# STorM32_NT_BGC_v330m.net
KiCad netlist of a schematic drawn in EAGLE
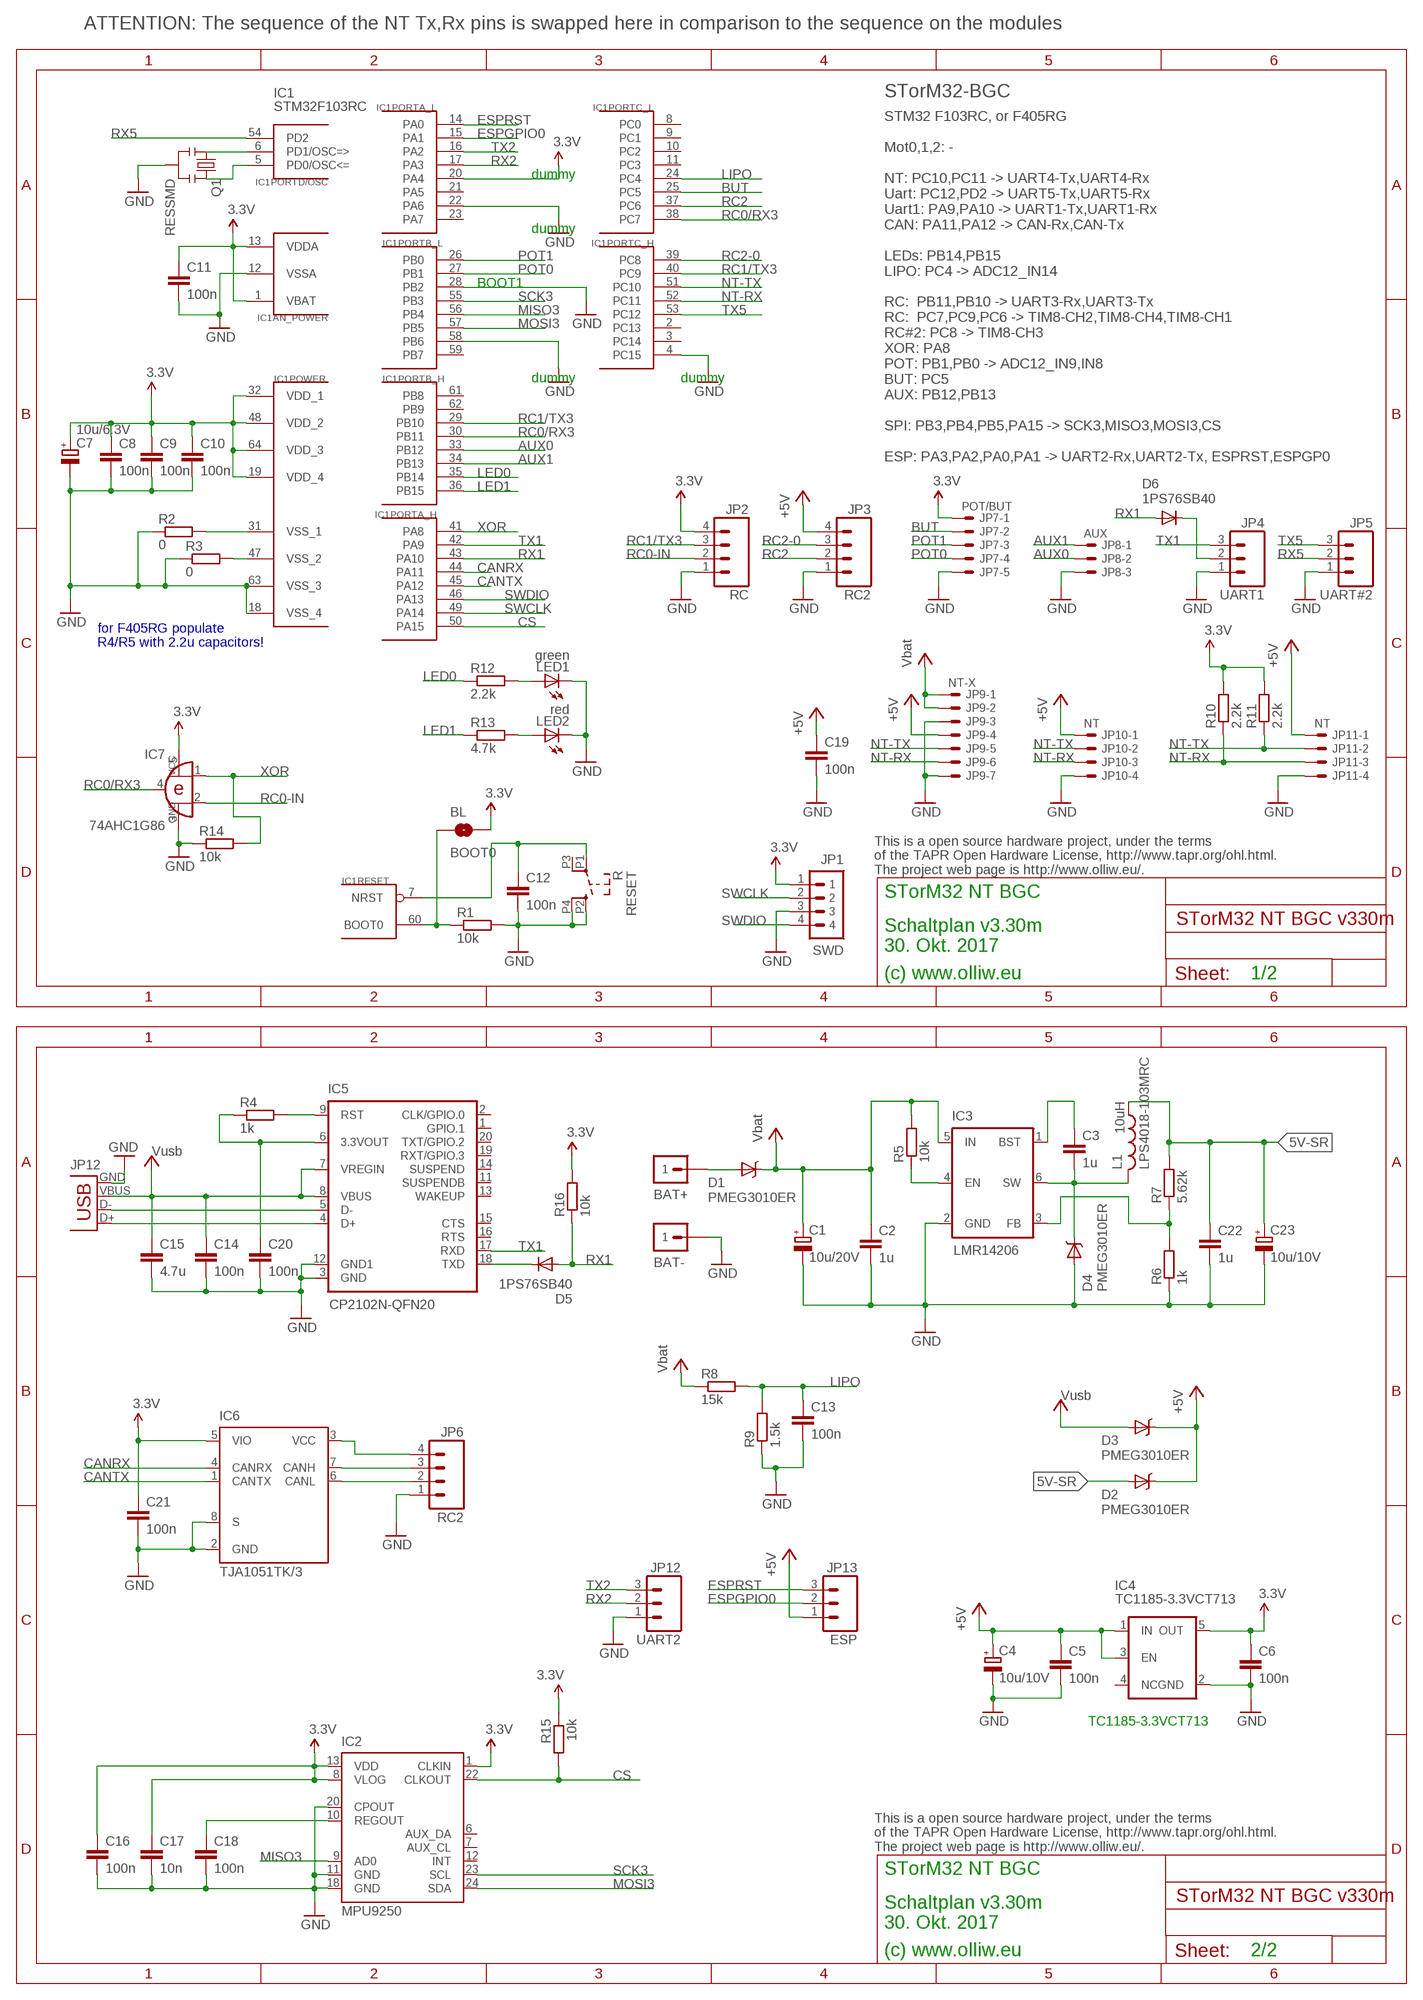
[diagram p0: schematic, sheet 1]

(export (version "E")
  (design (tool "Eeschema 10.0.6"))
  (components
    (comp (ref "BAT+")
      (value "M1X1")
      (footprint "eagle-import:1X1_WITHOUT")
      (libsource (lib "eagle-import") (part "M1X1"))
    )
    (comp (ref "BAT-")
      (value "M1X1")
      (footprint "eagle-import:1X1_WITHOUT")
      (libsource (lib "eagle-import") (part "M1X1"))
    )
    (comp (ref "BL")
      (value "BOOT0")
      (footprint "eagle-import:SJ_2S-NO")
      (libsource (lib "eagle-import") (part "SOLDERJUMPERNO"))
    )
    (comp (ref "C1")
      (value "10u/20V")
      (footprint "eagle-import:SMC_B")
      (libsource (lib "eagle-import") (part "CPOL-EUSMCB"))
    )
    (comp (ref "C2")
      (value "1u")
      (footprint "eagle-import:C0603")
      (libsource (lib "eagle-import") (part "C-EUC0603"))
    )
    (comp (ref "C3")
      (value "1u")
      (footprint "eagle-import:C0603")
      (libsource (lib "eagle-import") (part "C-EUC0603"))
    )
    (comp (ref "C4")
      (value "10u/10V")
      (footprint "eagle-import:SMC_A")
      (libsource (lib "eagle-import") (part "CPOL-EUSMCA"))
    )
    (comp (ref "C5")
      (value "100n")
      (footprint "eagle-import:C0603")
      (libsource (lib "eagle-import") (part "C-EUC0603"))
    )
    (comp (ref "C6")
      (value "100n")
      (footprint "eagle-import:C0402")
      (libsource (lib "eagle-import") (part "C-EUC0402"))
    )
    (comp (ref "C7")
      (value "10u/6.3V")
      (footprint "eagle-import:SMC_A")
      (libsource (lib "eagle-import") (part "CPOL-EUSMCA"))
    )
    (comp (ref "C8")
      (value "100n")
      (footprint "eagle-import:C0402")
      (libsource (lib "eagle-import") (part "C-EUC0402"))
    )
    (comp (ref "C9")
      (value "100n")
      (footprint "eagle-import:C0402")
      (libsource (lib "eagle-import") (part "C-EUC0402"))
    )
    (comp (ref "C10")
      (value "100n")
      (footprint "eagle-import:C0402")
      (libsource (lib "eagle-import") (part "C-EUC0402"))
    )
    (comp (ref "C11")
      (value "100n")
      (footprint "eagle-import:C0402")
      (libsource (lib "eagle-import") (part "C-EUC0402"))
    )
    (comp (ref "C12")
      (value "100n")
      (footprint "eagle-import:C0402")
      (libsource (lib "eagle-import") (part "C-EUC0402"))
    )
    (comp (ref "C13")
      (value "100n")
      (footprint "eagle-import:C0402")
      (libsource (lib "eagle-import") (part "C-EUC0402"))
    )
    (comp (ref "C14")
      (value "100n")
      (footprint "eagle-import:C0402")
      (libsource (lib "eagle-import") (part "C-EUC0402"))
    )
    (comp (ref "C15")
      (value "4.7u")
      (footprint "eagle-import:C0603")
      (libsource (lib "eagle-import") (part "C-EUC0603"))
    )
    (comp (ref "C16")
      (value "100n")
      (footprint "eagle-import:C0402")
      (libsource (lib "eagle-import") (part "C-EUC0402"))
    )
    (comp (ref "C17")
      (value "10n")
      (footprint "eagle-import:C0402")
      (libsource (lib "eagle-import") (part "C-EUC0402"))
    )
    (comp (ref "C18")
      (value "100n")
      (footprint "eagle-import:C0402")
      (libsource (lib "eagle-import") (part "C-EUC0402"))
    )
    (comp (ref "C19")
      (value "100n")
      (footprint "eagle-import:C0402")
      (libsource (lib "eagle-import") (part "C-EUC0402"))
    )
    (comp (ref "C20")
      (value "100n")
      (footprint "eagle-import:C0402")
      (libsource (lib "eagle-import") (part "C-EUC0402"))
    )
    (comp (ref "C21")
      (value "100n")
      (footprint "eagle-import:C0402")
      (libsource (lib "eagle-import") (part "C-EUC0402"))
    )
    (comp (ref "C22")
      (value "1u")
      (footprint "eagle-import:C0603")
      (libsource (lib "eagle-import") (part "C-EUC0603"))
    )
    (comp (ref "C23")
      (value "10u/10V")
      (footprint "eagle-import:SMC_A")
      (libsource (lib "eagle-import") (part "CPOL-EUSMCA"))
    )
    (comp (ref "D1")
      (value "PMEG3010ER")
      (footprint "eagle-import:SOD123W-DIODE")
      (libsource (lib "eagle-import") (part "DIODE-SCHOTTKYSOD123-W"))
    )
    (comp (ref "D2")
      (value "PMEG3010ER")
      (footprint "eagle-import:SOD123W-DIODE")
      (libsource (lib "eagle-import") (part "DIODE-SCHOTTKYSOD123-W"))
    )
    (comp (ref "D3")
      (value "PMEG3010ER")
      (footprint "eagle-import:SOD123W-DIODE")
      (libsource (lib "eagle-import") (part "DIODE-SCHOTTKYSOD123-W"))
    )
    (comp (ref "D4")
      (value "PMEG3010ER")
      (footprint "eagle-import:SOD123W-DIODE")
      (libsource (lib "eagle-import") (part "DIODE-SCHOTTKYSOD123-W"))
    )
    (comp (ref "D5")
      (value "1PS76SB40")
      (footprint "eagle-import:SOD110-R")
      (libsource (lib "eagle-import") (part "DIODE-SOD110-R"))
    )
    (comp (ref "D6")
      (value "1PS76SB40")
      (footprint "eagle-import:SOD110-R")
      (libsource (lib "eagle-import") (part "DIODE-SOD110-R"))
    )
    (comp (ref "IC1")
      (value "STM32F103RCT6")
      (footprint "eagle-import:TQFP64")
      (libsource (lib "eagle-import") (part "STM32F10XRXT6"))
    )
    (comp (ref "IC2")
      (value "MPU9250")
      (footprint "eagle-import:QFN-24-3X3")
      (libsource (lib "eagle-import") (part "IMU3000QFN-24-0.4MIL"))
    )
    (comp (ref "IC3")
      (value "LMR14206")
      (footprint "eagle-import:SOT23-6")
      (libsource (lib "eagle-import") (part "MP2359"))
    )
    (comp (ref "IC4")
      (value "TC1185-3.3VCT713")
      (footprint "eagle-import:SOT23-5")
      (libsource (lib "eagle-import") (part "V_REG_TPS76433SOT23-5"))
    )
    (comp (ref "IC5")
      (value "CP2102N-QFN20")
      (footprint "eagle-import:QFN20-CP2102N")
      (libsource (lib "eagle-import") (part "CP2102N-QFN20"))
    )
    (comp (ref "IC6")
      (value "TJA1051TK/3")
      (footprint "eagle-import:HVSON8")
      (libsource (lib "eagle-import") (part "TJA1051TK/3"))
    )
    (comp (ref "IC7")
      (value "74AHC1G86")
      (footprint "eagle-import:SOT23-5-VER1")
      (libsource (lib "eagle-import") (part "74AHC1G86"))
    )
    (comp (ref "JP1")
      (value "SWD")
      (footprint "eagle-import:4X1_1P27_OCT_BILEX")
      (libsource (lib "eagle-import") (part "P4X1_1P27-OCT_BILEX"))
    )
    (comp (ref "JP2")
      (value "RC")
      (footprint "eagle-import:1X04_NO_SILK")
      (libsource (lib "eagle-import") (part "M041X04_NO_SILK"))
    )
    (comp (ref "JP3")
      (value "RC2")
      (footprint "eagle-import:1X04_NO_SILK")
      (libsource (lib "eagle-import") (part "M041X04_NO_SILK"))
    )
    (comp (ref "JP4")
      (value "UART1")
      (footprint "eagle-import:1X03_NO_SILK")
      (libsource (lib "eagle-import") (part "M031X03_NO_SILK"))
    )
    (comp (ref "JP5")
      (value "UART#2")
      (footprint "eagle-import:1X03_NO_SILK")
      (libsource (lib "eagle-import") (part "M031X03_NO_SILK"))
    )
    (comp (ref "JP6")
      (value "RC2")
      (footprint "eagle-import:1X04_NO_SILK")
      (libsource (lib "eagle-import") (part "M041X04_NO_SILK"))
    )
    (comp (ref "JP7")
      (value "POT/BUT")
      (footprint "eagle-import:SM05B-SRSS-TB")
      (libsource (lib "eagle-import") (part "?M05B-SRSS-TBS"))
    )
    (comp (ref "JP8")
      (value "AUX")
      (footprint "eagle-import:SM03B-SRSS-TB")
      (libsource (lib "eagle-import") (part "?M03B-SRSS-TBS"))
    )
    (comp (ref "JP9")
      (value "NT-X")
      (footprint "eagle-import:SM07B-SRSS-TB")
      (libsource (lib "eagle-import") (part "?M07B-SRSS-TBS"))
    )
    (comp (ref "JP10")
      (value "NT")
      (footprint "eagle-import:SM04B-SRSS-TB")
      (libsource (lib "eagle-import") (part "?M04B-SRSS-TBS"))
    )
    (comp (ref "JP11")
      (value "NT")
      (footprint "eagle-import:SM04B-SRSS-TB")
      (libsource (lib "eagle-import") (part "?M04B-SRSS-TBS"))
    )
    (comp (ref "JP12")
      (value "UART2")
      (footprint "eagle-import:1X03_NO_SILK")
      (libsource (lib "eagle-import") (part "M031X03_NO_SILK"))
    )
    (comp (ref "JP13")
      (value "ESP")
      (footprint "eagle-import:1X03_NO_SILK")
      (libsource (lib "eagle-import") (part "M031X03_NO_SILK"))
    )
    (comp (ref "L1")
      (value "LPS4018-103MRC")
      (footprint "eagle-import:L4X4")
      (libsource (lib "eagle-import") (part "L"))
    )
    (comp (ref "LED1")
      (value "green")
      (footprint "eagle-import:CHIPLED_0603")
      (libsource (lib "eagle-import") (part "LEDCHIPLED_0603"))
    )
    (comp (ref "LED2")
      (value "red")
      (footprint "eagle-import:CHIPLED_0603")
      (libsource (lib "eagle-import") (part "LEDCHIPLED_0603"))
    )
    (comp (ref "Q1")
      (value "RESSMD")
      (footprint "eagle-import:RESONATOR-SMD")
      (libsource (lib "eagle-import") (part "RESONATORSMD"))
    )
    (comp (ref "R1")
      (value "10k")
      (footprint "eagle-import:R0402")
      (libsource (lib "eagle-import") (part "R-EU_R0402"))
    )
    (comp (ref "R2")
      (value "0")
      (footprint "eagle-import:R0402")
      (libsource (lib "eagle-import") (part "R-EU_R0402"))
    )
    (comp (ref "R3")
      (value "0")
      (footprint "eagle-import:R0402")
      (libsource (lib "eagle-import") (part "R-EU_R0402"))
    )
    (comp (ref "R4")
      (value "1k")
      (footprint "eagle-import:R0402")
      (libsource (lib "eagle-import") (part "R-EU_R0402"))
    )
    (comp (ref "R5")
      (value "10k")
      (footprint "eagle-import:R0402")
      (libsource (lib "eagle-import") (part "R-EU_R0402"))
    )
    (comp (ref "R6")
      (value "1k")
      (footprint "eagle-import:R0402")
      (libsource (lib "eagle-import") (part "R-EU_R0402"))
    )
    (comp (ref "R7")
      (value "5.62k")
      (footprint "eagle-import:R0402")
      (libsource (lib "eagle-import") (part "R-EU_R0402"))
    )
    (comp (ref "R8")
      (value "15k")
      (footprint "eagle-import:R0402")
      (libsource (lib "eagle-import") (part "R-EU_R0402"))
    )
    (comp (ref "R9")
      (value "1.5k")
      (footprint "eagle-import:R0402")
      (libsource (lib "eagle-import") (part "R-EU_R0402"))
    )
    (comp (ref "R10")
      (value "2.2k")
      (footprint "eagle-import:R0402")
      (libsource (lib "eagle-import") (part "R-EU_R0402"))
    )
    (comp (ref "R11")
      (value "2.2k")
      (footprint "eagle-import:R0402")
      (libsource (lib "eagle-import") (part "R-EU_R0402"))
    )
    (comp (ref "R12")
      (value "2.2k")
      (footprint "eagle-import:R0402")
      (libsource (lib "eagle-import") (part "R-EU_R0402"))
    )
    (comp (ref "R13")
      (value "4.7k")
      (footprint "eagle-import:R0402")
      (libsource (lib "eagle-import") (part "R-EU_R0402"))
    )
    (comp (ref "R14")
      (value "10k")
      (footprint "eagle-import:R0402")
      (libsource (lib "eagle-import") (part "R-EU_R0402"))
    )
    (comp (ref "R15")
      (value "10k")
      (footprint "eagle-import:R0402")
      (libsource (lib "eagle-import") (part "R-EU_R0402"))
    )
    (comp (ref "R16")
      (value "10k")
      (footprint "eagle-import:R0402")
      (libsource (lib "eagle-import") (part "R-EU_R0402"))
    )
    (comp (ref "RESET")
      (value "R")
      (footprint "eagle-import:TACTILE-SWITCH-SMD-RIGHT-TL1014")
      (libsource (lib "eagle-import") (part "SWITCH-SMD-RIGHT-TL1014"))
    )
    (comp (ref "USB")
      (value "Amphenol 10118192-0001LF")
      (footprint "eagle-import:USB-MICROB")
      (libsource (lib "eagle-import") (part "USB-MICROB"))
    )
  )
  (nets
    (net (code "1") (name "+5V") (class "Default")
      (node (ref "C19") (pin "1") (pinfunction "1_1") (pintype "passive"))
      (node (ref "C4") (pin "+") (pinfunction "+_+") (pintype "passive"))
      (node (ref "C5") (pin "1") (pinfunction "1_1") (pintype "passive"))
      (node (ref "D2") (pin "C") (pinfunction "C_C") (pintype "passive"))
      (node (ref "D3") (pin "C") (pinfunction "C_C") (pintype "passive"))
      (node (ref "IC4") (pin "1") (pinfunction "IN_1") (pintype "power_in"))
      (node (ref "IC4") (pin "3") (pinfunction "EN_3") (pintype "input"))
      (node (ref "JP10") (pin "1") (pinfunction "S_1") (pintype "passive"))
      (node (ref "JP11") (pin "1") (pinfunction "S_1") (pintype "passive"))
      (node (ref "JP13") (pin "1") (pinfunction "1_1") (pintype "passive"))
      (node (ref "JP3") (pin "4") (pinfunction "4_4") (pintype "passive"))
      (node (ref "JP9") (pin "4") (pinfunction "S_4") (pintype "passive"))
    )
    (net (code "2") (name "/AUX0") (class "Default")
      (node (ref "IC1") (pin "33") (pinfunction "PB12_33") (pintype "bidirectional"))
      (node (ref "JP8") (pin "2") (pinfunction "S_2") (pintype "passive"))
    )
    (net (code "3") (name "/AUX1") (class "Default")
      (node (ref "IC1") (pin "34") (pinfunction "PB13_34") (pintype "bidirectional"))
      (node (ref "JP8") (pin "1") (pinfunction "S_1") (pintype "passive"))
    )
    (net (code "4") (name "/BUT") (class "Default")
      (node (ref "IC1") (pin "25") (pinfunction "PC5_25") (pintype "bidirectional"))
      (node (ref "JP7") (pin "2") (pinfunction "S_2") (pintype "passive"))
    )
    (net (code "5") (name "/CANRX") (class "Default")
      (node (ref "IC1") (pin "44") (pinfunction "PA11_44") (pintype "bidirectional"))
      (node (ref "IC6") (pin "4") (pinfunction "CANRX_4") (pintype "output"))
    )
    (net (code "6") (name "/CANTX") (class "Default")
      (node (ref "IC1") (pin "45") (pinfunction "PA12_45") (pintype "bidirectional"))
      (node (ref "IC6") (pin "1") (pinfunction "CANTX_1") (pintype "input"))
    )
    (net (code "7") (name "/CS") (class "Default")
      (node (ref "IC1") (pin "50") (pinfunction "PA15_50") (pintype "bidirectional"))
      (node (ref "IC2") (pin "22") (pinfunction "CLKOUT_22") (pintype "bidirectional"))
      (node (ref "R15") (pin "2") (pinfunction "2_2") (pintype "passive"))
    )
    (net (code "8") (name "/ESPGPIO0") (class "Default")
      (node (ref "IC1") (pin "15") (pinfunction "PA1_15") (pintype "bidirectional"))
      (node (ref "JP13") (pin "2") (pinfunction "2_2") (pintype "passive"))
    )
    (net (code "9") (name "/ESPRST") (class "Default")
      (node (ref "IC1") (pin "14") (pinfunction "PA0_14") (pintype "bidirectional"))
      (node (ref "JP13") (pin "3") (pinfunction "3_3") (pintype "passive"))
    )
    (net (code "10") (name "/LED0") (class "Default")
      (node (ref "IC1") (pin "35") (pinfunction "PB14_35") (pintype "bidirectional"))
      (node (ref "R12") (pin "1") (pinfunction "1_1") (pintype "passive"))
    )
    (net (code "11") (name "/LED1") (class "Default")
      (node (ref "IC1") (pin "36") (pinfunction "PB15_36") (pintype "bidirectional"))
      (node (ref "R13") (pin "1") (pinfunction "1_1") (pintype "passive"))
    )
    (net (code "12") (name "/LIPO") (class "Default")
      (node (ref "C13") (pin "1") (pinfunction "1_1") (pintype "passive"))
      (node (ref "IC1") (pin "24") (pinfunction "PC4_24") (pintype "bidirectional"))
      (node (ref "R8") (pin "2") (pinfunction "2_2") (pintype "passive"))
      (node (ref "R9") (pin "2") (pinfunction "2_2") (pintype "passive"))
    )
    (net (code "13") (name "/MISO3") (class "Default")
      (node (ref "IC1") (pin "56") (pinfunction "PB4_56") (pintype "bidirectional"))
      (node (ref "IC2") (pin "9") (pinfunction "AD0_9") (pintype "bidirectional"))
    )
    (net (code "14") (name "/MOSI3") (class "Default")
      (node (ref "IC1") (pin "57") (pinfunction "PB5_57") (pintype "bidirectional"))
      (node (ref "IC2") (pin "24") (pinfunction "SDA_24") (pintype "bidirectional"))
    )
    (net (code "15") (name "/NT-RX") (class "Default")
      (node (ref "IC1") (pin "52") (pinfunction "PC11_52") (pintype "bidirectional"))
      (node (ref "JP10") (pin "3") (pinfunction "S_3") (pintype "passive"))
      (node (ref "JP11") (pin "3") (pinfunction "S_3") (pintype "passive"))
      (node (ref "JP9") (pin "6") (pinfunction "S_6") (pintype "passive"))
      (node (ref "R10") (pin "1") (pinfunction "1_1") (pintype "passive"))
    )
    (net (code "16") (name "/NT-TX") (class "Default")
      (node (ref "IC1") (pin "51") (pinfunction "PC10_51") (pintype "bidirectional"))
      (node (ref "JP10") (pin "2") (pinfunction "S_2") (pintype "passive"))
      (node (ref "JP11") (pin "2") (pinfunction "S_2") (pintype "passive"))
      (node (ref "JP9") (pin "5") (pinfunction "S_5") (pintype "passive"))
      (node (ref "R11") (pin "1") (pinfunction "1_1") (pintype "passive"))
    )
    (net (code "17") (name "/POT0") (class "Default")
      (node (ref "IC1") (pin "27") (pinfunction "PB1_27") (pintype "bidirectional"))
      (node (ref "JP7") (pin "4") (pinfunction "S_4") (pintype "passive"))
    )
    (net (code "18") (name "/POT1") (class "Default")
      (node (ref "IC1") (pin "26") (pinfunction "PB0_26") (pintype "bidirectional"))
      (node (ref "JP7") (pin "3") (pinfunction "S_3") (pintype "passive"))
    )
    (net (code "19") (name "/RC0-IN") (class "Default")
      (node (ref "IC7") (pin "2") (pinfunction "I1_2") (pintype "input"))
      (node (ref "JP2") (pin "2") (pinfunction "2_2") (pintype "passive"))
    )
    (net (code "20") (name "/RC0{slash}RX3") (class "Default")
      (node (ref "IC1") (pin "30") (pinfunction "PB11_30") (pintype "bidirectional"))
      (node (ref "IC1") (pin "38") (pinfunction "PC7_38") (pintype "bidirectional"))
      (node (ref "IC7") (pin "4") (pinfunction "O_4") (pintype "output"))
    )
    (net (code "21") (name "/RC1{slash}TX3") (class "Default")
      (node (ref "IC1") (pin "29") (pinfunction "PB10_29") (pintype "bidirectional"))
      (node (ref "IC1") (pin "40") (pinfunction "PC9_40") (pintype "bidirectional"))
      (node (ref "JP2") (pin "3") (pinfunction "3_3") (pintype "passive"))
    )
    (net (code "22") (name "/RC2") (class "Default")
      (node (ref "IC1") (pin "37") (pinfunction "PC6_37") (pintype "bidirectional"))
      (node (ref "JP3") (pin "2") (pinfunction "2_2") (pintype "passive"))
    )
    (net (code "23") (name "/RC2-0") (class "Default")
      (node (ref "IC1") (pin "39") (pinfunction "PC8_39") (pintype "bidirectional"))
      (node (ref "JP3") (pin "3") (pinfunction "3_3") (pintype "passive"))
    )
    (net (code "24") (name "/RX1") (class "Default")
      (node (ref "D5") (pin "A") (pinfunction "A_A") (pintype "passive"))
      (node (ref "D6") (pin "A") (pinfunction "A_A") (pintype "passive"))
      (node (ref "IC1") (pin "43") (pinfunction "PA10_43") (pintype "bidirectional"))
      (node (ref "R16") (pin "1") (pinfunction "1_1") (pintype "passive"))
    )
    (net (code "25") (name "/RX2") (class "Default")
      (node (ref "IC1") (pin "17") (pinfunction "PA3_17") (pintype "bidirectional"))
      (node (ref "JP12") (pin "2") (pinfunction "2_2") (pintype "passive"))
    )
    (net (code "26") (name "/RX5") (class "Default")
      (node (ref "IC1") (pin "54") (pinfunction "PD2_54") (pintype "bidirectional"))
      (node (ref "JP5") (pin "2") (pinfunction "2_2") (pintype "passive"))
    )
    (net (code "27") (name "/SCK3") (class "Default")
      (node (ref "IC1") (pin "55") (pinfunction "PB3_55") (pintype "bidirectional"))
      (node (ref "IC2") (pin "23") (pinfunction "SCL_23") (pintype "bidirectional"))
    )
    (net (code "28") (name "/SWCLK") (class "Default")
      (node (ref "IC1") (pin "49") (pinfunction "PA14_49") (pintype "bidirectional"))
      (node (ref "JP1") (pin "2") (pinfunction "2_2") (pintype "passive"))
    )
    (net (code "29") (name "/SWDIO") (class "Default")
      (node (ref "IC1") (pin "46") (pinfunction "PA13_46") (pintype "bidirectional"))
      (node (ref "JP1") (pin "4") (pinfunction "4_4") (pintype "passive"))
    )
    (net (code "30") (name "/TX1") (class "Default")
      (node (ref "IC1") (pin "42") (pinfunction "PA9_42") (pintype "bidirectional"))
      (node (ref "IC5") (pin "17") (pinfunction "RXD_17") (pintype "input"))
      (node (ref "JP4") (pin "3") (pinfunction "3_3") (pintype "passive"))
    )
    (net (code "31") (name "/TX2") (class "Default")
      (node (ref "IC1") (pin "16") (pinfunction "PA2_16") (pintype "bidirectional"))
      (node (ref "JP12") (pin "3") (pinfunction "3_3") (pintype "passive"))
    )
    (net (code "32") (name "/TX5") (class "Default")
      (node (ref "IC1") (pin "53") (pinfunction "PC12_53") (pintype "bidirectional"))
      (node (ref "JP5") (pin "3") (pinfunction "3_3") (pintype "passive"))
    )
    (net (code "33") (name "/XOR") (class "Default")
      (node (ref "IC1") (pin "41") (pinfunction "PA8_41") (pintype "bidirectional"))
      (node (ref "IC7") (pin "1") (pinfunction "I0_1") (pintype "input"))
      (node (ref "R14") (pin "2") (pinfunction "2_2") (pintype "passive"))
    )
    (net (code "34") (name "3.3V") (class "Default")
      (node (ref "BL") (pin "2") (pinfunction "2_2") (pintype "passive"))
      (node (ref "C10") (pin "1") (pinfunction "1_1") (pintype "passive"))
      (node (ref "C11") (pin "1") (pinfunction "1_1") (pintype "passive"))
      (node (ref "C16") (pin "1") (pinfunction "1_1") (pintype "passive"))
      (node (ref "C17") (pin "1") (pinfunction "1_1") (pintype "passive"))
      (node (ref "C21") (pin "1") (pinfunction "1_1") (pintype "passive"))
      (node (ref "C6") (pin "1") (pinfunction "1_1") (pintype "passive"))
      (node (ref "C7") (pin "+") (pinfunction "+_+") (pintype "passive"))
      (node (ref "C8") (pin "1") (pinfunction "1_1") (pintype "passive"))
      (node (ref "C9") (pin "1") (pinfunction "1_1") (pintype "passive"))
      (node (ref "IC1") (pin "1") (pinfunction "VBAT_1") (pintype "power_in"))
      (node (ref "IC1") (pin "13") (pinfunction "VDDA_13") (pintype "power_in"))
      (node (ref "IC1") (pin "19") (pinfunction "VDD_4_19") (pintype "power_in"))
      (node (ref "IC1") (pin "20") (pinfunction "PA4_20") (pintype "bidirectional"))
      (node (ref "IC1") (pin "32") (pinfunction "VDD_1_32") (pintype "power_in"))
      (node (ref "IC1") (pin "48") (pinfunction "VDD_2_48") (pintype "power_in"))
      (node (ref "IC1") (pin "64") (pinfunction "VDD_3_64") (pintype "power_in"))
      (node (ref "IC2") (pin "1") (pinfunction "CLKIN_1") (pintype "bidirectional"))
      (node (ref "IC2") (pin "13") (pinfunction "VDD_13") (pintype "bidirectional"))
      (node (ref "IC2") (pin "8") (pinfunction "VLOG_8") (pintype "bidirectional"))
      (node (ref "IC4") (pin "5") (pinfunction "OUT_5") (pintype "output"))
      (node (ref "IC6") (pin "5") (pinfunction "VIO_5") (pintype "power_in"))
      (node (ref "IC7") (pin "5") (pinfunction "VCC_5") (pintype "power_in"))
      (node (ref "JP1") (pin "1") (pinfunction "1_1") (pintype "passive"))
      (node (ref "JP2") (pin "4") (pinfunction "4_4") (pintype "passive"))
      (node (ref "JP7") (pin "1") (pinfunction "S_1") (pintype "passive"))
      (node (ref "R10") (pin "2") (pinfunction "2_2") (pintype "passive"))
      (node (ref "R11") (pin "2") (pinfunction "2_2") (pintype "passive"))
      (node (ref "R15") (pin "1") (pinfunction "1_1") (pintype "passive"))
      (node (ref "R16") (pin "2") (pinfunction "2_2") (pintype "passive"))
    )
    (net (code "35") (name "5V-SR") (class "Default")
      (node (ref "C22") (pin "1") (pinfunction "1_1") (pintype "passive"))
      (node (ref "C23") (pin "+") (pinfunction "+_+") (pintype "passive"))
      (node (ref "D2") (pin "A") (pinfunction "A_A") (pintype "passive"))
      (node (ref "L1") (pin "1") (pinfunction "1_1") (pintype "passive"))
      (node (ref "R7") (pin "2") (pinfunction "2_2") (pintype "passive"))
    )
    (net (code "36") (name "GND") (class "Default")
      (node (ref "BAT-") (pin "1") (pinfunction "1_1") (pintype "passive"))
      (node (ref "C1") (pin "-") (pinfunction "-_-") (pintype "passive"))
      (node (ref "C10") (pin "2") (pinfunction "2_2") (pintype "passive"))
      (node (ref "C11") (pin "2") (pinfunction "2_2") (pintype "passive"))
      (node (ref "C12") (pin "2") (pinfunction "2_2") (pintype "passive"))
      (node (ref "C13") (pin "2") (pinfunction "2_2") (pintype "passive"))
      (node (ref "C14") (pin "2") (pinfunction "2_2") (pintype "passive"))
      (node (ref "C15") (pin "2") (pinfunction "2_2") (pintype "passive"))
      (node (ref "C16") (pin "2") (pinfunction "2_2") (pintype "passive"))
      (node (ref "C17") (pin "2") (pinfunction "2_2") (pintype "passive"))
      (node (ref "C18") (pin "2") (pinfunction "2_2") (pintype "passive"))
      (node (ref "C19") (pin "2") (pinfunction "2_2") (pintype "passive"))
      (node (ref "C2") (pin "2") (pinfunction "2_2") (pintype "passive"))
      (node (ref "C20") (pin "2") (pinfunction "2_2") (pintype "passive"))
      (node (ref "C21") (pin "2") (pinfunction "2_2") (pintype "passive"))
      (node (ref "C22") (pin "2") (pinfunction "2_2") (pintype "passive"))
      (node (ref "C23") (pin "-") (pinfunction "-_-") (pintype "passive"))
      (node (ref "C4") (pin "-") (pinfunction "-_-") (pintype "passive"))
      (node (ref "C5") (pin "2") (pinfunction "2_2") (pintype "passive"))
      (node (ref "C6") (pin "2") (pinfunction "2_2") (pintype "passive"))
      (node (ref "C7") (pin "-") (pinfunction "-_-") (pintype "passive"))
      (node (ref "C8") (pin "2") (pinfunction "2_2") (pintype "passive"))
      (node (ref "C9") (pin "2") (pinfunction "2_2") (pintype "passive"))
      (node (ref "D4") (pin "A") (pinfunction "A_A") (pintype "passive"))
      (node (ref "IC1") (pin "12") (pinfunction "VSSA_12") (pintype "power_in"))
      (node (ref "IC1") (pin "18") (pinfunction "VSS_4_18") (pintype "power_in"))
      (node (ref "IC1") (pin "22") (pinfunction "PA6_22") (pintype "bidirectional"))
      (node (ref "IC1") (pin "28") (pinfunction "PB2_28") (pintype "bidirectional"))
      (node (ref "IC1") (pin "4") (pinfunction "PC15_4") (pintype "bidirectional"))
      (node (ref "IC1") (pin "58") (pinfunction "PB6_58") (pintype "bidirectional"))
      (node (ref "IC1") (pin "63") (pinfunction "VSS_3_63") (pintype "power_in"))
      (node (ref "IC2") (pin "11") (pinfunction "GND_11") (pintype "bidirectional"))
      (node (ref "IC2") (pin "18") (pinfunction "GND_18") (pintype "bidirectional"))
      (node (ref "IC2") (pin "20") (pinfunction "CPOUT_20") (pintype "bidirectional"))
      (node (ref "IC3") (pin "2") (pinfunction "GND_2") (pintype "power_in"))
      (node (ref "IC4") (pin "2") (pinfunction "GND_2") (pintype "power_in"))
      (node (ref "IC5") (pin "12") (pinfunction "GND1_12") (pintype "power_in"))
      (node (ref "IC5") (pin "3") (pinfunction "GND_3") (pintype "power_in"))
      (node (ref "IC6") (pin "2") (pinfunction "GND_2") (pintype "power_in"))
      (node (ref "IC6") (pin "8") (pinfunction "S_8") (pintype "input"))
      (node (ref "IC7") (pin "3") (pinfunction "GND_3") (pintype "power_in"))
      (node (ref "JP1") (pin "3") (pinfunction "3_3") (pintype "passive"))
      (node (ref "JP10") (pin "4") (pinfunction "S_4") (pintype "passive"))
      (node (ref "JP11") (pin "4") (pinfunction "S_4") (pintype "passive"))
      (node (ref "JP12") (pin "1") (pinfunction "1_1") (pintype "passive"))
      (node (ref "JP2") (pin "1") (pinfunction "1_1") (pintype "passive"))
      (node (ref "JP3") (pin "1") (pinfunction "1_1") (pintype "passive"))
      (node (ref "JP4") (pin "1") (pinfunction "1_1") (pintype "passive"))
      (node (ref "JP5") (pin "1") (pinfunction "1_1") (pintype "passive"))
      (node (ref "JP6") (pin "1") (pinfunction "1_1") (pintype "passive"))
      (node (ref "JP7") (pin "5") (pinfunction "S_5") (pintype "passive"))
      (node (ref "JP8") (pin "3") (pinfunction "S_3") (pintype "passive"))
      (node (ref "JP9") (pin "3") (pinfunction "S_3") (pintype "passive"))
      (node (ref "JP9") (pin "7") (pinfunction "S_7") (pintype "passive"))
      (node (ref "LED1") (pin "C") (pinfunction "C_C") (pintype "passive"))
      (node (ref "LED2") (pin "C") (pinfunction "C_C") (pintype "passive"))
      (node (ref "Q1") (pin "2") (pinfunction "2_2") (pintype "passive"))
      (node (ref "R1") (pin "2") (pinfunction "2_2") (pintype "passive"))
      (node (ref "R14") (pin "1") (pinfunction "1_1") (pintype "passive"))
      (node (ref "R2") (pin "1") (pinfunction "1_1") (pintype "passive"))
      (node (ref "R3") (pin "1") (pinfunction "1_1") (pintype "passive"))
      (node (ref "R6") (pin "1") (pinfunction "1_1") (pintype "passive"))
      (node (ref "R9") (pin "1") (pinfunction "1_1") (pintype "passive"))
      (node (ref "RESET") (pin "P2") (pinfunction "1_P2") (pintype "passive"))
      (node (ref "RESET") (pin "P4") (pinfunction "2_P4") (pintype "passive"))
      (node (ref "USB") (pin "GND") (pinfunction "GND_GND") (pintype "bidirectional"))
    )
    (net (code "37") (name "Net-(BAT+-Pad1)") (class "Default")
      (node (ref "BAT+") (pin "1") (pinfunction "1_1") (pintype "passive"))
      (node (ref "D1") (pin "A") (pinfunction "A_A") (pintype "passive"))
    )
    (net (code "38") (name "Net-(D6-PadC)") (class "Default")
      (node (ref "D6") (pin "C") (pinfunction "C_C") (pintype "passive"))
      (node (ref "JP4") (pin "2") (pinfunction "2_2") (pintype "passive"))
    )
    (net (code "39") (name "Net-(IC1H-PD0{slash}OSC<=)") (class "Default")
      (node (ref "IC1") (pin "5") (pinfunction "PD0/OSC<=_5") (pintype "bidirectional"))
      (node (ref "Q1") (pin "3") (pinfunction "3_3") (pintype "passive"))
    )
    (net (code "40") (name "Net-(IC1H-PD1{slash}OSC=>)") (class "Default")
      (node (ref "IC1") (pin "6") (pinfunction "PD1/OSC=>_6") (pintype "bidirectional"))
      (node (ref "Q1") (pin "1") (pinfunction "1_1") (pintype "passive"))
    )
    (net (code "41") (name "Net-(IC1I-VSS_1)") (class "Default")
      (node (ref "IC1") (pin "31") (pinfunction "VSS_1_31") (pintype "power_in"))
      (node (ref "R2") (pin "2") (pinfunction "2_2") (pintype "passive"))
    )
    (net (code "42") (name "Net-(IC1I-VSS_2)") (class "Default")
      (node (ref "IC1") (pin "47") (pinfunction "VSS_2_47") (pintype "power_in"))
      (node (ref "R3") (pin "2") (pinfunction "2_2") (pintype "passive"))
    )
    (net (code "43") (name "Net-(IC1J-BOOT0)") (class "Default")
      (node (ref "BL") (pin "1") (pinfunction "1_1") (pintype "passive"))
      (node (ref "IC1") (pin "60") (pinfunction "BOOT0_60") (pintype "input"))
      (node (ref "R1") (pin "1") (pinfunction "1_1") (pintype "passive"))
    )
    (net (code "44") (name "Net-(IC1J-NRST)") (class "Default")
      (node (ref "C12") (pin "1") (pinfunction "1_1") (pintype "passive"))
      (node (ref "IC1") (pin "7") (pinfunction "NRST_7") (pintype "input"))
      (node (ref "RESET") (pin "P1") (pinfunction "3_P1") (pintype "passive"))
    )
    (net (code "45") (name "Net-(IC2-REGOUT)") (class "Default")
      (node (ref "C18") (pin "1") (pinfunction "1_1") (pintype "passive"))
      (node (ref "IC2") (pin "10") (pinfunction "REGOUT_10") (pintype "bidirectional"))
    )
    (net (code "46") (name "Net-(IC3-BST)") (class "Default")
      (node (ref "C3") (pin "1") (pinfunction "1_1") (pintype "passive"))
      (node (ref "IC3") (pin "1") (pinfunction "BST_1") (pintype "output"))
    )
    (net (code "47") (name "Net-(IC3-EN)") (class "Default")
      (node (ref "IC3") (pin "4") (pinfunction "EN_4") (pintype "input"))
      (node (ref "R5") (pin "1") (pinfunction "1_1") (pintype "passive"))
    )
    (net (code "48") (name "Net-(IC3-FB)") (class "Default")
      (node (ref "IC3") (pin "3") (pinfunction "FB_3") (pintype "input"))
      (node (ref "R6") (pin "2") (pinfunction "2_2") (pintype "passive"))
      (node (ref "R7") (pin "1") (pinfunction "1_1") (pintype "passive"))
    )
    (net (code "49") (name "Net-(IC3-SW)") (class "Default")
      (node (ref "C3") (pin "2") (pinfunction "2_2") (pintype "passive"))
      (node (ref "D4") (pin "C") (pinfunction "C_C") (pintype "passive"))
      (node (ref "IC3") (pin "6") (pinfunction "SW_6") (pintype "output"))
      (node (ref "L1") (pin "2") (pinfunction "2_2") (pintype "passive"))
    )
    (net (code "50") (name "Net-(IC5-3.3VOUT)") (class "Default")
      (node (ref "C20") (pin "1") (pinfunction "1_1") (pintype "passive"))
      (node (ref "IC5") (pin "6") (pinfunction "3.3VOUT_6") (pintype "power_in"))
      (node (ref "R4") (pin "1") (pinfunction "1_1") (pintype "passive"))
    )
    (net (code "51") (name "Net-(IC5-D+)") (class "Default")
      (node (ref "IC5") (pin "4") (pinfunction "D+_4") (pintype "bidirectional"))
      (node (ref "USB") (pin "D+") (pinfunction "D+_D+") (pintype "bidirectional"))
    )
    (net (code "52") (name "Net-(IC5-D-)") (class "Default")
      (node (ref "IC5") (pin "5") (pinfunction "D-_5") (pintype "bidirectional"))
      (node (ref "USB") (pin "D-") (pinfunction "D-_D-") (pintype "bidirectional"))
    )
    (net (code "53") (name "Net-(IC5-RST)") (class "Default")
      (node (ref "IC5") (pin "9") (pinfunction "RST_9") (pintype "input"))
      (node (ref "R4") (pin "2") (pinfunction "2_2") (pintype "passive"))
    )
    (net (code "54") (name "Net-(IC5-TXD)") (class "Default")
      (node (ref "D5") (pin "C") (pinfunction "C_C") (pintype "passive"))
      (node (ref "IC5") (pin "18") (pinfunction "TXD_18") (pintype "output"))
    )
    (net (code "55") (name "Net-(IC6-CANH)") (class "Default")
      (node (ref "IC6") (pin "7") (pinfunction "CANH_7") (pintype "bidirectional"))
      (node (ref "JP6") (pin "3") (pinfunction "3_3") (pintype "passive"))
    )
    (net (code "56") (name "Net-(IC6-CANL)") (class "Default")
      (node (ref "IC6") (pin "6") (pinfunction "CANL_6") (pintype "bidirectional"))
      (node (ref "JP6") (pin "2") (pinfunction "2_2") (pintype "passive"))
    )
    (net (code "57") (name "Net-(IC6-VCC)") (class "Default")
      (node (ref "IC6") (pin "3") (pinfunction "VCC_3") (pintype "power_in"))
      (node (ref "JP6") (pin "4") (pinfunction "4_4") (pintype "passive"))
    )
    (net (code "58") (name "Net-(LED1-PadA)") (class "Default")
      (node (ref "LED1") (pin "A") (pinfunction "A_A") (pintype "passive"))
      (node (ref "R12") (pin "2") (pinfunction "2_2") (pintype "passive"))
    )
    (net (code "59") (name "Net-(LED2-PadA)") (class "Default")
      (node (ref "LED2") (pin "A") (pinfunction "A_A") (pintype "passive"))
      (node (ref "R13") (pin "2") (pinfunction "2_2") (pintype "passive"))
    )
    (net (code "60") (name "Vbat") (class "Default")
      (node (ref "C1") (pin "+") (pinfunction "+_+") (pintype "passive"))
      (node (ref "C2") (pin "1") (pinfunction "1_1") (pintype "passive"))
      (node (ref "D1") (pin "C") (pinfunction "C_C") (pintype "passive"))
      (node (ref "IC3") (pin "5") (pinfunction "IN_5") (pintype "power_in"))
      (node (ref "JP9") (pin "1") (pinfunction "S_1") (pintype "passive"))
      (node (ref "JP9") (pin "2") (pinfunction "S_2") (pintype "passive"))
      (node (ref "R5") (pin "2") (pinfunction "2_2") (pintype "passive"))
      (node (ref "R8") (pin "1") (pinfunction "1_1") (pintype "passive"))
    )
    (net (code "61") (name "Vusb") (class "Default")
      (node (ref "C14") (pin "1") (pinfunction "1_1") (pintype "passive"))
      (node (ref "C15") (pin "1") (pinfunction "1_1") (pintype "passive"))
      (node (ref "D3") (pin "A") (pinfunction "A_A") (pintype "passive"))
      (node (ref "IC5") (pin "7") (pinfunction "VREGIN_7") (pintype "power_in"))
      (node (ref "IC5") (pin "8") (pinfunction "VBUS_8") (pintype "input"))
      (node (ref "USB") (pin "VBUS") (pinfunction "VBUS_VBUS") (pintype "bidirectional"))
    )
    (net (code "62") (name "unconnected-(IC1C-PA5-Pad21)") (class "Default")
      (node (ref "IC1") (pin "21") (pinfunction "PA5_21") (pintype "bidirectional"))
    )
    (net (code "63") (name "unconnected-(IC1C-PA7-Pad23)") (class "Default")
      (node (ref "IC1") (pin "23") (pinfunction "PA7_23") (pintype "bidirectional"))
    )
    (net (code "64") (name "unconnected-(IC1D-PB8-Pad61)") (class "Default")
      (node (ref "IC1") (pin "61") (pinfunction "PB8_61") (pintype "bidirectional"))
    )
    (net (code "65") (name "unconnected-(IC1D-PB9-Pad62)") (class "Default")
      (node (ref "IC1") (pin "62") (pinfunction "PB9_62") (pintype "bidirectional"))
    )
    (net (code "66") (name "unconnected-(IC1E-PB7-Pad59)") (class "Default")
      (node (ref "IC1") (pin "59") (pinfunction "PB7_59") (pintype "bidirectional"))
    )
    (net (code "67") (name "unconnected-(IC1F-PC13-Pad2)") (class "Default")
      (node (ref "IC1") (pin "2") (pinfunction "PC13_2") (pintype "bidirectional"))
    )
    (net (code "68") (name "unconnected-(IC1F-PC14-Pad3)") (class "Default")
      (node (ref "IC1") (pin "3") (pinfunction "PC14_3") (pintype "bidirectional"))
    )
    (net (code "69") (name "unconnected-(IC1G-PC0-Pad8)") (class "Default")
      (node (ref "IC1") (pin "8") (pinfunction "PC0_8") (pintype "bidirectional"))
    )
    (net (code "70") (name "unconnected-(IC1G-PC1-Pad9)") (class "Default")
      (node (ref "IC1") (pin "9") (pinfunction "PC1_9") (pintype "bidirectional"))
    )
    (net (code "71") (name "unconnected-(IC1G-PC2-Pad10)") (class "Default")
      (node (ref "IC1") (pin "10") (pinfunction "PC2_10") (pintype "bidirectional"))
    )
    (net (code "72") (name "unconnected-(IC1G-PC3-Pad11)") (class "Default")
      (node (ref "IC1") (pin "11") (pinfunction "PC3_11") (pintype "bidirectional"))
    )
    (net (code "73") (name "unconnected-(IC2-AUX_CL-Pad7)") (class "Default")
      (node (ref "IC2") (pin "7") (pinfunction "AUX_CL_7") (pintype "bidirectional"))
    )
    (net (code "74") (name "unconnected-(IC2-AUX_DA-Pad6)") (class "Default")
      (node (ref "IC2") (pin "6") (pinfunction "AUX_DA_6") (pintype "bidirectional"))
    )
    (net (code "75") (name "unconnected-(IC2-INT-Pad12)") (class "Default")
      (node (ref "IC2") (pin "12") (pinfunction "INT_12") (pintype "bidirectional"))
    )
    (net (code "76") (name "unconnected-(IC4-NC-Pad4)") (class "Default")
      (node (ref "IC4") (pin "4") (pinfunction "NC_4") (pintype "passive"))
    )
    (net (code "77") (name "unconnected-(IC5-CLK{slash}GPIO.0-Pad2)") (class "Default")
      (node (ref "IC5") (pin "2") (pinfunction "CLK/GPIO.0_2") (pintype "bidirectional"))
    )
    (net (code "78") (name "unconnected-(IC5-CTS-Pad15)") (class "Default")
      (node (ref "IC5") (pin "15") (pinfunction "CTS_15") (pintype "input"))
    )
    (net (code "79") (name "unconnected-(IC5-GPIO.1-Pad1)") (class "Default")
      (node (ref "IC5") (pin "1") (pinfunction "GPIO.1_1") (pintype "bidirectional"))
    )
    (net (code "80") (name "unconnected-(IC5-RTS-Pad16)") (class "Default")
      (node (ref "IC5") (pin "16") (pinfunction "RTS_16") (pintype "output"))
    )
    (net (code "81") (name "unconnected-(IC5-RXT{slash}GPIO.3-Pad19)") (class "Default")
      (node (ref "IC5") (pin "19") (pinfunction "RXT/GPIO.3_19") (pintype "bidirectional"))
    )
    (net (code "82") (name "unconnected-(IC5-SUSPEND-Pad14)") (class "Default")
      (node (ref "IC5") (pin "14") (pinfunction "SUSPEND_14") (pintype "output"))
    )
    (net (code "83") (name "unconnected-(IC5-SUSPENDB-Pad11)") (class "Default")
      (node (ref "IC5") (pin "11") (pinfunction "SUSPENDB_11") (pintype "output"))
    )
    (net (code "84") (name "unconnected-(IC5-TXT{slash}GPIO.2-Pad20)") (class "Default")
      (node (ref "IC5") (pin "20") (pinfunction "TXT/GPIO.2_20") (pintype "bidirectional"))
    )
    (net (code "85") (name "unconnected-(IC5-WAKEUP-Pad13)") (class "Default")
      (node (ref "IC5") (pin "13") (pinfunction "WAKEUP_13") (pintype "input"))
    )
    (net (code "86") (name "unconnected-(RESET-4-PadP3)") (class "Default")
      (node (ref "RESET") (pin "P3") (pinfunction "4_P3") (pintype "passive"))
    )
  )
)
